# main.net
KiCad netlist of a schematic drawn in Altium Designer
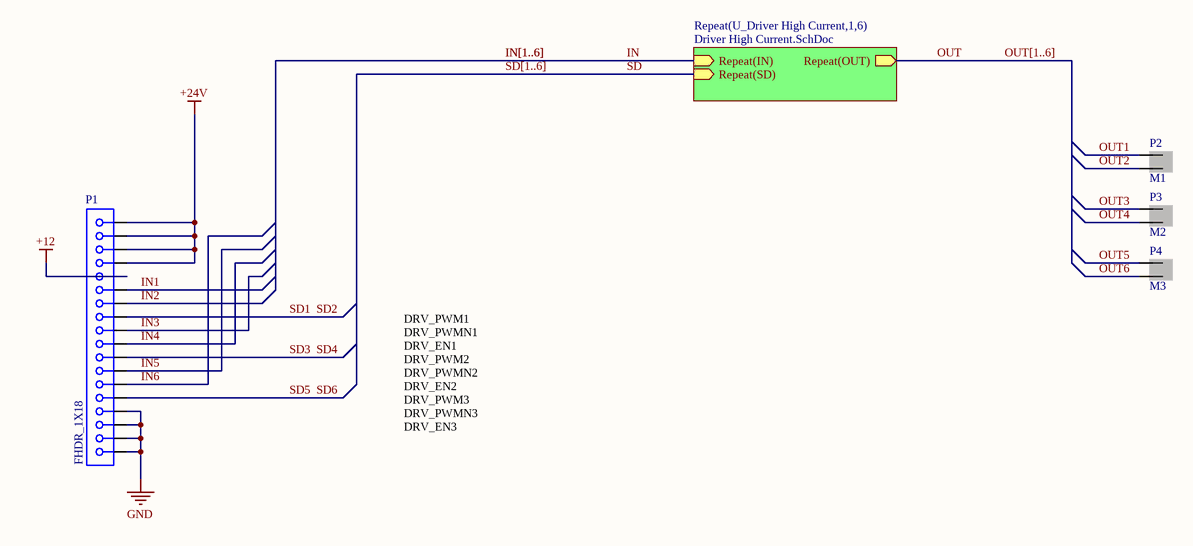
[diagram p0: main.SchDoc]

(export (version "E")
  (design (tool "Eeschema 10.0.6"))
  (components
    (comp (ref "P1")
      (value "FHDR_1X18")
      (footprint "FHDR1X18-254P")
      (description "Female Header 1X18")
      (libsource (lib "SJ Sockets & Connectors") (part "FHDR_1X18"))
    )
    (comp (ref "P2")
      (value "M1")
      (footprint "ATX 2PIN")
      (description "ATX 2PIN")
      (libsource (lib "MAD libs") (part "ATX 2PIN"))
    )
    (comp (ref "P3")
      (value "M2")
      (footprint "ATX 2PIN")
      (description "ATX 2PIN")
      (libsource (lib "MAD libs") (part "ATX 2PIN"))
    )
    (comp (ref "P4")
      (value "M3")
      (footprint "ATX 2PIN")
      (description "ATX 2PIN")
      (libsource (lib "MAD libs") (part "ATX 2PIN"))
    )
  )
  (nets
    (net (code "1") (name "+12") (class "Default")
      (node (ref "P1") (pin "5") (pinfunction "5_5") (pintype "passive"))
    )
    (net (code "2") (name "+24V") (class "Default")
      (node (ref "P1") (pin "1") (pinfunction "1_1") (pintype "passive"))
      (node (ref "P1") (pin "2") (pinfunction "2_2") (pintype "passive"))
      (node (ref "P1") (pin "3") (pinfunction "3_3") (pintype "passive"))
      (node (ref "P1") (pin "4") (pinfunction "4_4") (pintype "passive"))
    )
    (net (code "4") (name "/IN1") (class "Default")
      (node (ref "P1") (pin "6") (pinfunction "6_6") (pintype "passive"))
    )
    (net (code "5") (name "/IN2") (class "Default")
      (node (ref "P1") (pin "7") (pinfunction "7_7") (pintype "passive"))
    )
    (net (code "6") (name "/IN3") (class "Default")
      (node (ref "P1") (pin "9") (pinfunction "9_9") (pintype "passive"))
    )
    (net (code "7") (name "/IN4") (class "Default")
      (node (ref "P1") (pin "10") (pinfunction "10_10") (pintype "passive"))
    )
    (net (code "8") (name "/IN5") (class "Default")
      (node (ref "P1") (pin "12") (pinfunction "12_12") (pintype "passive"))
    )
    (net (code "9") (name "/IN6") (class "Default")
      (node (ref "P1") (pin "13") (pinfunction "13_13") (pintype "passive"))
    )
    (net (code "12") (name "/OUT1") (class "Default")
      (node (ref "P2") (pin "1") (pinfunction "1_1") (pintype "passive"))
    )
    (net (code "13") (name "/OUT2") (class "Default")
      (node (ref "P2") (pin "2") (pinfunction "2_2") (pintype "passive"))
    )
    (net (code "14") (name "/OUT3") (class "Default")
      (node (ref "P3") (pin "1") (pinfunction "1_1") (pintype "passive"))
    )
    (net (code "15") (name "/OUT4") (class "Default")
      (node (ref "P3") (pin "2") (pinfunction "2_2") (pintype "passive"))
    )
    (net (code "16") (name "/OUT5") (class "Default")
      (node (ref "P4") (pin "1") (pinfunction "1_1") (pintype "passive"))
    )
    (net (code "17") (name "/OUT6") (class "Default")
      (node (ref "P4") (pin "2") (pinfunction "2_2") (pintype "passive"))
    )
    (net (code "19") (name "/SD2") (class "Default")
      (node (ref "P1") (pin "8") (pinfunction "8_8") (pintype "passive"))
    )
    (net (code "20") (name "/SD4") (class "Default")
      (node (ref "P1") (pin "11") (pinfunction "11_11") (pintype "passive"))
    )
    (net (code "21") (name "/SD6") (class "Default")
      (node (ref "P1") (pin "14") (pinfunction "14_14") (pintype "passive"))
    )
    (net (code "23") (name "GND") (class "Default")
      (node (ref "P1") (pin "15") (pinfunction "15_15") (pintype "passive"))
      (node (ref "P1") (pin "16") (pinfunction "16_16") (pintype "passive"))
      (node (ref "P1") (pin "17") (pinfunction "17_17") (pintype "passive"))
      (node (ref "P1") (pin "18") (pinfunction "18_18") (pintype "passive"))
    )
  )
)
